# can-isolator-1_1.net
KiCad netlist of a schematic drawn in EAGLE
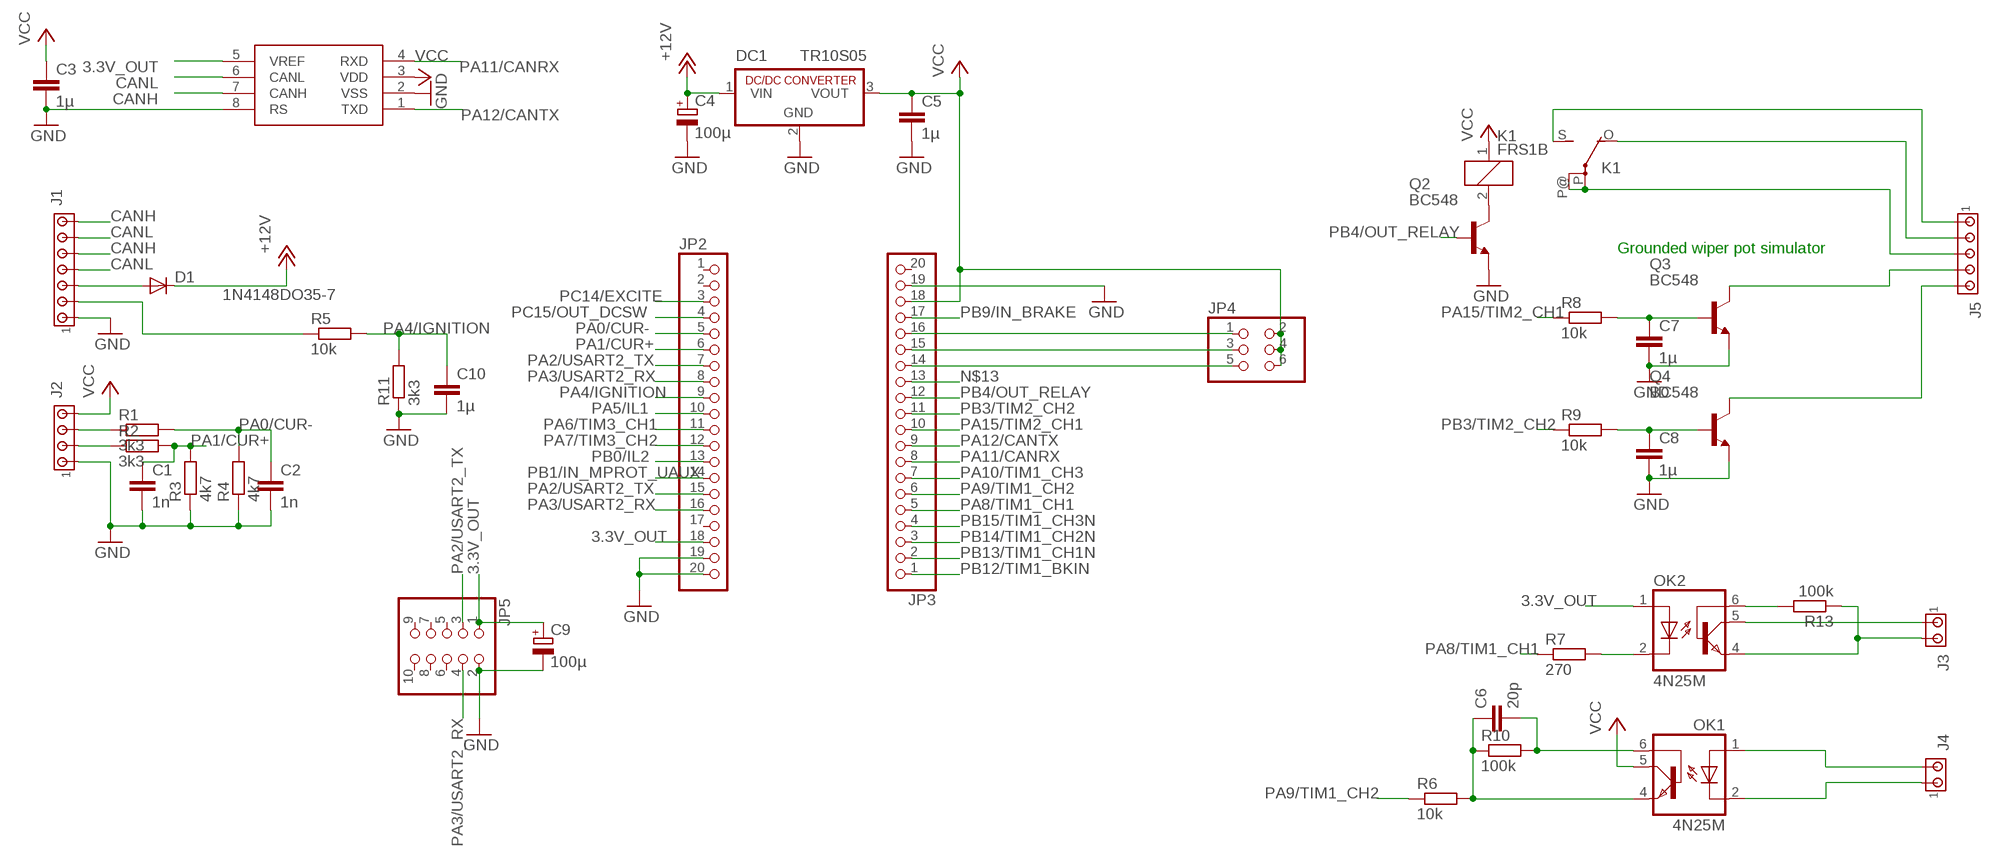
[diagram p0: schematic, sheet 1]

(export (version "E")
  (design (tool "Eeschema 10.0.6"))
  (components
    (comp (ref "C1")
      (value "1n")
      (footprint "eagle-import:C025-024X044")
      (libsource (lib "eagle-import") (part "C-EU025-024X044"))
    )
    (comp (ref "C2")
      (value "1n")
      (footprint "eagle-import:C025-024X044")
      (libsource (lib "eagle-import") (part "C-EU025-024X044"))
    )
    (comp (ref "C3")
      (value "1µ")
      (footprint "eagle-import:C025-024X044")
      (libsource (lib "eagle-import") (part "C-EU025-024X044"))
    )
    (comp (ref "C4")
      (value "100µ")
      (footprint "eagle-import:E2-5")
      (libsource (lib "eagle-import") (part "CPOL-EUE2-5"))
    )
    (comp (ref "C5")
      (value "1µ")
      (footprint "eagle-import:C025-024X044")
      (libsource (lib "eagle-import") (part "C-EU025-024X044"))
    )
    (comp (ref "C6")
      (value "20p")
      (footprint "eagle-import:C025-024X044")
      (libsource (lib "eagle-import") (part "C-EU025-024X044"))
    )
    (comp (ref "C7")
      (value "1µ")
      (footprint "eagle-import:C025-024X044")
      (libsource (lib "eagle-import") (part "C-EU025-024X044"))
    )
    (comp (ref "C8")
      (value "1µ")
      (footprint "eagle-import:C025-024X044")
      (libsource (lib "eagle-import") (part "C-EU025-024X044"))
    )
    (comp (ref "C9")
      (value "100µ")
      (footprint "eagle-import:E2-5")
      (libsource (lib "eagle-import") (part "CPOL-EUE2-5"))
    )
    (comp (ref "C10")
      (value "1µ")
      (footprint "eagle-import:C025-024X044")
      (libsource (lib "eagle-import") (part "C-EU025-024X044"))
    )
    (comp (ref "D1")
      (value "1N4148DO35-7")
      (footprint "eagle-import:DO35-7")
      (libsource (lib "eagle-import") (part "1N4148DO35-7"))
    )
    (comp (ref "DC1")
      (value "TR10S05")
      (footprint "eagle-import:SIP3")
      (libsource (lib "eagle-import") (part "R-78C-1.05.0"))
    )
    (comp (ref "IC1")
      (value "MCP2562P")
      (footprint "eagle-import:DIL08")
      (libsource (lib "eagle-import") (part "MCP2551P"))
    )
    (comp (ref "J1")
      (value "MTA07-100")
      (footprint "eagle-import:10X07MTA")
      (libsource (lib "eagle-import") (part "MTA07-100"))
    )
    (comp (ref "J2")
      (value "MTA04-100")
      (footprint "eagle-import:10X04MTA")
      (libsource (lib "eagle-import") (part "MTA04-100"))
    )
    (comp (ref "J3")
      (value "MTA02-100")
      (footprint "eagle-import:10X02MTA")
      (libsource (lib "eagle-import") (part "MTA02-100"))
    )
    (comp (ref "J4")
      (value "MTA02-100")
      (footprint "eagle-import:10X02MTA")
      (libsource (lib "eagle-import") (part "MTA02-100"))
    )
    (comp (ref "J5")
      (value "MTA05-100")
      (footprint "eagle-import:10X05MTA")
      (libsource (lib "eagle-import") (part "MTA05-100"))
    )
    (comp (ref "JP2")
      (value "PINHD-1X20")
      (footprint "eagle-import:1X20")
      (libsource (lib "eagle-import") (part "PINHD-1X20"))
    )
    (comp (ref "JP3")
      (value "PINHD-1X20")
      (footprint "eagle-import:1X20")
      (libsource (lib "eagle-import") (part "PINHD-1X20"))
    )
    (comp (ref "JP4")
      (value "PINHD-2X3")
      (footprint "eagle-import:2X03")
      (libsource (lib "eagle-import") (part "PINHD-2X3"))
    )
    (comp (ref "JP5")
      (value "PINHD-2X5/90")
      (footprint "eagle-import:2X05_90")
      (libsource (lib "eagle-import") (part "PINHD-2X5/90"))
    )
    (comp (ref "K1")
      (value "FRS1B")
      (footprint "eagle-import:FRS1B")
      (libsource (lib "eagle-import") (part "FRS1B"))
    )
    (comp (ref "OK1")
      (value "4N25M")
      (footprint "eagle-import:DIL06")
      (fields (field (name "MPN") "4N25-M"))
      (libsource (lib "eagle-import") (part "4N?M25"))
    )
    (comp (ref "OK2")
      (value "4N25M")
      (footprint "eagle-import:DIL06")
      (fields (field (name "MPN") "4N25-M"))
      (libsource (lib "eagle-import") (part "4N?M25"))
    )
    (comp (ref "Q2")
      (value "BC548")
      (footprint "eagle-import:TO92-EBC")
      (libsource (lib "eagle-import") (part "BC548"))
    )
    (comp (ref "Q3")
      (value "BC548")
      (footprint "eagle-import:TO92-EBC")
      (libsource (lib "eagle-import") (part "BC548"))
    )
    (comp (ref "Q4")
      (value "BC548")
      (footprint "eagle-import:TO92-EBC")
      (libsource (lib "eagle-import") (part "BC548"))
    )
    (comp (ref "R1")
      (value "3k3")
      (footprint "eagle-import:0207_10")
      (libsource (lib "eagle-import") (part "R-EU_0207/10"))
    )
    (comp (ref "R2")
      (value "3k3")
      (footprint "eagle-import:0207_10")
      (libsource (lib "eagle-import") (part "R-EU_0207/10"))
    )
    (comp (ref "R3")
      (value "4k7")
      (footprint "eagle-import:0207_10")
      (libsource (lib "eagle-import") (part "R-EU_0207/10"))
    )
    (comp (ref "R4")
      (value "4k7")
      (footprint "eagle-import:0207_10")
      (libsource (lib "eagle-import") (part "R-EU_0207/10"))
    )
    (comp (ref "R5")
      (value "10k")
      (footprint "eagle-import:0207_10")
      (libsource (lib "eagle-import") (part "R-EU_0207/10"))
    )
    (comp (ref "R6")
      (value "10k")
      (footprint "eagle-import:0207_10")
      (libsource (lib "eagle-import") (part "R-EU_0207/10"))
    )
    (comp (ref "R7")
      (value "270")
      (footprint "eagle-import:0207_10")
      (libsource (lib "eagle-import") (part "R-EU_0207/10"))
    )
    (comp (ref "R8")
      (value "10k")
      (footprint "eagle-import:0207_10")
      (libsource (lib "eagle-import") (part "R-EU_0207/10"))
    )
    (comp (ref "R9")
      (value "10k")
      (footprint "eagle-import:0207_10")
      (libsource (lib "eagle-import") (part "R-EU_0207/10"))
    )
    (comp (ref "R10")
      (value "100k")
      (footprint "eagle-import:0207_10")
      (libsource (lib "eagle-import") (part "R-EU_0207/10"))
    )
    (comp (ref "R11")
      (value "3k3")
      (footprint "eagle-import:0207_10")
      (libsource (lib "eagle-import") (part "R-EU_0207/10"))
    )
    (comp (ref "R13")
      (value "100k")
      (footprint "eagle-import:0207_10")
      (libsource (lib "eagle-import") (part "R-EU_0207/10"))
    )
  )
  (nets
    (net (code "1") (name "+12V") (class "Default")
      (node (ref "C4") (pin "+") (pinfunction "+_+") (pintype "passive"))
      (node (ref "D1") (pin "C") (pinfunction "C_C") (pintype "passive"))
      (node (ref "DC1") (pin "1") (pinfunction "VIN_1") (pintype "passive"))
    )
    (net (code "2") (name "/3.3V_OUT") (class "Default")
      (node (ref "C9") (pin "+") (pinfunction "+_+") (pintype "passive"))
      (node (ref "IC1") (pin "5") (pinfunction "VREF_5") (pintype "bidirectional"))
      (node (ref "JP2") (pin "18") (pinfunction "18_18") (pintype "passive"))
      (node (ref "JP5") (pin "1") (pinfunction "1_1") (pintype "passive"))
      (node (ref "OK2") (pin "1") (pinfunction "A_1") (pintype "passive"))
    )
    (net (code "3") (name "/CANH") (class "Default")
      (node (ref "IC1") (pin "7") (pinfunction "CANH_7") (pintype "bidirectional"))
      (node (ref "J1") (pin "5") (pinfunction "5_5") (pintype "passive"))
      (node (ref "J1") (pin "7") (pinfunction "7_7") (pintype "passive"))
    )
    (net (code "4") (name "/CANL") (class "Default")
      (node (ref "IC1") (pin "6") (pinfunction "CANL_6") (pintype "bidirectional"))
      (node (ref "J1") (pin "4") (pinfunction "4_4") (pintype "passive"))
      (node (ref "J1") (pin "6") (pinfunction "6_6") (pintype "passive"))
    )
    (net (code "5") (name "/N$13") (class "Default")
      (node (ref "JP3") (pin "13") (pinfunction "13_13") (pintype "passive"))
    )
    (net (code "6") (name "/PA0{slash}CUR-") (class "Default")
      (node (ref "C2") (pin "1") (pinfunction "1_1") (pintype "passive"))
      (node (ref "JP2") (pin "5") (pinfunction "5_5") (pintype "passive"))
      (node (ref "R1") (pin "2") (pinfunction "2_2") (pintype "passive"))
      (node (ref "R4") (pin "2") (pinfunction "2_2") (pintype "passive"))
    )
    (net (code "7") (name "/PA1{slash}CUR+") (class "Default")
      (node (ref "C1") (pin "1") (pinfunction "1_1") (pintype "passive"))
      (node (ref "JP2") (pin "6") (pinfunction "6_6") (pintype "passive"))
      (node (ref "R2") (pin "2") (pinfunction "2_2") (pintype "passive"))
      (node (ref "R3") (pin "2") (pinfunction "2_2") (pintype "passive"))
    )
    (net (code "8") (name "/PA2{slash}USART2_TX") (class "Default")
      (node (ref "JP2") (pin "15") (pinfunction "15_15") (pintype "passive"))
      (node (ref "JP2") (pin "7") (pinfunction "7_7") (pintype "passive"))
      (node (ref "JP5") (pin "3") (pinfunction "3_3") (pintype "passive"))
    )
    (net (code "9") (name "/PA3{slash}USART2_RX") (class "Default")
      (node (ref "JP2") (pin "16") (pinfunction "16_16") (pintype "passive"))
      (node (ref "JP2") (pin "8") (pinfunction "8_8") (pintype "passive"))
      (node (ref "JP5") (pin "4") (pinfunction "4_4") (pintype "passive"))
    )
    (net (code "10") (name "/PA4{slash}IGNITION") (class "Default")
      (node (ref "C10") (pin "1") (pinfunction "1_1") (pintype "passive"))
      (node (ref "JP2") (pin "9") (pinfunction "9_9") (pintype "passive"))
      (node (ref "R11") (pin "2") (pinfunction "2_2") (pintype "passive"))
      (node (ref "R5") (pin "2") (pinfunction "2_2") (pintype "passive"))
    )
    (net (code "11") (name "/PA5{slash}IL1") (class "Default")
      (node (ref "JP2") (pin "10") (pinfunction "10_10") (pintype "passive"))
    )
    (net (code "12") (name "/PA6{slash}TIM3_CH1") (class "Default")
      (node (ref "JP2") (pin "11") (pinfunction "11_11") (pintype "passive"))
    )
    (net (code "13") (name "/PA7{slash}TIM3_CH2") (class "Default")
      (node (ref "JP2") (pin "12") (pinfunction "12_12") (pintype "passive"))
    )
    (net (code "14") (name "/PA8{slash}TIM1_CH1") (class "Default")
      (node (ref "JP3") (pin "5") (pinfunction "5_5") (pintype "passive"))
      (node (ref "R7") (pin "1") (pinfunction "1_1") (pintype "passive"))
    )
    (net (code "15") (name "/PA9{slash}TIM1_CH2") (class "Default")
      (node (ref "JP3") (pin "6") (pinfunction "6_6") (pintype "passive"))
      (node (ref "R6") (pin "1") (pinfunction "1_1") (pintype "passive"))
    )
    (net (code "16") (name "/PA10{slash}TIM1_CH3") (class "Default")
      (node (ref "JP3") (pin "7") (pinfunction "7_7") (pintype "passive"))
    )
    (net (code "17") (name "/PA11{slash}CANRX") (class "Default")
      (node (ref "IC1") (pin "4") (pinfunction "RXD_4") (pintype "bidirectional"))
      (node (ref "JP3") (pin "8") (pinfunction "8_8") (pintype "passive"))
    )
    (net (code "18") (name "/PA12{slash}CANTX") (class "Default")
      (node (ref "IC1") (pin "1") (pinfunction "TXD_1") (pintype "bidirectional"))
      (node (ref "JP3") (pin "9") (pinfunction "9_9") (pintype "passive"))
    )
    (net (code "19") (name "/PA15{slash}TIM2_CH1") (class "Default")
      (node (ref "JP3") (pin "10") (pinfunction "10_10") (pintype "passive"))
      (node (ref "R8") (pin "1") (pinfunction "1_1") (pintype "passive"))
    )
    (net (code "20") (name "/PB0{slash}IL2") (class "Default")
      (node (ref "JP2") (pin "13") (pinfunction "13_13") (pintype "passive"))
    )
    (net (code "21") (name "/PB1{slash}IN_MPROT_UAUX") (class "Default")
      (node (ref "JP2") (pin "14") (pinfunction "14_14") (pintype "passive"))
    )
    (net (code "22") (name "/PB3{slash}TIM2_CH2") (class "Default")
      (node (ref "JP3") (pin "11") (pinfunction "11_11") (pintype "passive"))
      (node (ref "R9") (pin "1") (pinfunction "1_1") (pintype "passive"))
    )
    (net (code "23") (name "/PB4{slash}OUT_RELAY") (class "Default")
      (node (ref "JP3") (pin "12") (pinfunction "12_12") (pintype "passive"))
      (node (ref "Q2") (pin "B") (pinfunction "B_B") (pintype "passive"))
    )
    (net (code "24") (name "/PB9{slash}IN_BRAKE") (class "Default")
      (node (ref "JP3") (pin "17") (pinfunction "17_17") (pintype "passive"))
    )
    (net (code "25") (name "/PB12{slash}TIM1_BKIN") (class "Default")
      (node (ref "JP3") (pin "1") (pinfunction "1_1") (pintype "passive"))
    )
    (net (code "26") (name "/PB13{slash}TIM1_CH1N") (class "Default")
      (node (ref "JP3") (pin "2") (pinfunction "2_2") (pintype "passive"))
    )
    (net (code "27") (name "/PB14{slash}TIM1_CH2N") (class "Default")
      (node (ref "JP3") (pin "3") (pinfunction "3_3") (pintype "passive"))
    )
    (net (code "28") (name "/PB15{slash}TIM1_CH3N") (class "Default")
      (node (ref "JP3") (pin "4") (pinfunction "4_4") (pintype "passive"))
    )
    (net (code "29") (name "/PC14{slash}EXCITE") (class "Default")
      (node (ref "JP2") (pin "3") (pinfunction "3_3") (pintype "passive"))
    )
    (net (code "30") (name "/PC15{slash}OUT_DCSW") (class "Default")
      (node (ref "JP2") (pin "4") (pinfunction "4_4") (pintype "passive"))
    )
    (net (code "31") (name "GND") (class "Default")
      (node (ref "C1") (pin "2") (pinfunction "2_2") (pintype "passive"))
      (node (ref "C10") (pin "2") (pinfunction "2_2") (pintype "passive"))
      (node (ref "C2") (pin "2") (pinfunction "2_2") (pintype "passive"))
      (node (ref "C3") (pin "2") (pinfunction "2_2") (pintype "passive"))
      (node (ref "C4") (pin "-") (pinfunction "-_-") (pintype "passive"))
      (node (ref "C5") (pin "2") (pinfunction "2_2") (pintype "passive"))
      (node (ref "C7") (pin "2") (pinfunction "2_2") (pintype "passive"))
      (node (ref "C8") (pin "2") (pinfunction "2_2") (pintype "passive"))
      (node (ref "C9") (pin "-") (pinfunction "-_-") (pintype "passive"))
      (node (ref "DC1") (pin "2") (pinfunction "GND_2") (pintype "passive"))
      (node (ref "IC1") (pin "2") (pinfunction "VSS_2") (pintype "bidirectional"))
      (node (ref "IC1") (pin "8") (pinfunction "RS_8") (pintype "bidirectional"))
      (node (ref "J1") (pin "1") (pinfunction "1_1") (pintype "passive"))
      (node (ref "J2") (pin "1") (pinfunction "1_1") (pintype "passive"))
      (node (ref "JP2") (pin "19") (pinfunction "19_19") (pintype "passive"))
      (node (ref "JP2") (pin "20") (pinfunction "20_20") (pintype "passive"))
      (node (ref "JP3") (pin "19") (pinfunction "19_19") (pintype "passive"))
      (node (ref "JP5") (pin "2") (pinfunction "2_2") (pintype "passive"))
      (node (ref "Q2") (pin "E") (pinfunction "E_E") (pintype "passive"))
      (node (ref "Q3") (pin "E") (pinfunction "E_E") (pintype "passive"))
      (node (ref "Q4") (pin "E") (pinfunction "E_E") (pintype "passive"))
      (node (ref "R11") (pin "1") (pinfunction "1_1") (pintype "passive"))
      (node (ref "R3") (pin "1") (pinfunction "1_1") (pintype "passive"))
      (node (ref "R4") (pin "1") (pinfunction "1_1") (pintype "passive"))
    )
    (net (code "32") (name "Net-(C7-Pad1)") (class "Default")
      (node (ref "C7") (pin "1") (pinfunction "1_1") (pintype "passive"))
      (node (ref "Q3") (pin "B") (pinfunction "B_B") (pintype "passive"))
      (node (ref "R8") (pin "2") (pinfunction "2_2") (pintype "passive"))
    )
    (net (code "33") (name "Net-(C8-Pad1)") (class "Default")
      (node (ref "C8") (pin "1") (pinfunction "1_1") (pintype "passive"))
      (node (ref "Q4") (pin "B") (pinfunction "B_B") (pintype "passive"))
      (node (ref "R9") (pin "2") (pinfunction "2_2") (pintype "passive"))
    )
    (net (code "34") (name "Net-(D1-PadA)") (class "Default")
      (node (ref "D1") (pin "A") (pinfunction "A_A") (pintype "passive"))
      (node (ref "J1") (pin "3") (pinfunction "3_3") (pintype "passive"))
    )
    (net (code "35") (name "Net-(J1-Pad2)") (class "Default")
      (node (ref "J1") (pin "2") (pinfunction "2_2") (pintype "passive"))
      (node (ref "R5") (pin "1") (pinfunction "1_1") (pintype "passive"))
    )
    (net (code "36") (name "Net-(J2-Pad2)") (class "Default")
      (node (ref "J2") (pin "2") (pinfunction "2_2") (pintype "passive"))
      (node (ref "R2") (pin "1") (pinfunction "1_1") (pintype "passive"))
    )
    (net (code "37") (name "Net-(J2-Pad3)") (class "Default")
      (node (ref "J2") (pin "3") (pinfunction "3_3") (pintype "passive"))
      (node (ref "R1") (pin "1") (pinfunction "1_1") (pintype "passive"))
    )
    (net (code "38") (name "Net-(J5-Pad1)") (class "Default")
      (node (ref "J5") (pin "1") (pinfunction "1_1") (pintype "passive"))
      (node (ref "K1") (pin "S") (pinfunction "S_S") (pintype "passive"))
    )
    (net (code "39") (name "Net-(J5-Pad2)") (class "Default")
      (node (ref "J5") (pin "2") (pinfunction "2_2") (pintype "passive"))
      (node (ref "K1") (pin "O") (pinfunction "O_O") (pintype "passive"))
    )
    (net (code "40") (name "Net-(J5-Pad3)") (class "Default")
      (node (ref "J5") (pin "3") (pinfunction "3_3") (pintype "passive"))
      (node (ref "K1") (pin "P") (pinfunction "P_P") (pintype "passive"))
      (node (ref "K1") (pin "P@") (pinfunction "P_P@") (pintype "passive"))
    )
    (net (code "41") (name "Net-(J5-Pad4)") (class "Default")
      (node (ref "J5") (pin "4") (pinfunction "4_4") (pintype "passive"))
      (node (ref "Q3") (pin "C") (pinfunction "C_C") (pintype "passive"))
    )
    (net (code "42") (name "Net-(J5-Pad5)") (class "Default")
      (node (ref "J5") (pin "5") (pinfunction "5_5") (pintype "passive"))
      (node (ref "Q4") (pin "C") (pinfunction "C_C") (pintype "passive"))
    )
    (net (code "43") (name "Net-(JP3-Pad14)") (class "Default")
      (node (ref "JP3") (pin "14") (pinfunction "14_14") (pintype "passive"))
      (node (ref "JP4") (pin "5") (pinfunction "5_5") (pintype "passive"))
    )
    (net (code "44") (name "Net-(JP3-Pad15)") (class "Default")
      (node (ref "JP3") (pin "15") (pinfunction "15_15") (pintype "passive"))
      (node (ref "JP4") (pin "3") (pinfunction "3_3") (pintype "passive"))
    )
    (net (code "45") (name "Net-(JP3-Pad16)") (class "Default")
      (node (ref "JP3") (pin "16") (pinfunction "16_16") (pintype "passive"))
      (node (ref "JP4") (pin "1") (pinfunction "1_1") (pintype "passive"))
    )
    (net (code "46") (name "Net-(K1-Pad2)") (class "Default")
      (node (ref "K1") (pin "2") (pinfunction "2_2") (pintype "passive"))
      (node (ref "Q2") (pin "C") (pinfunction "C_C") (pintype "passive"))
    )
    (net (code "47") (name "Net-(OK1-A)") (class "Default")
      (node (ref "J4") (pin "2") (pinfunction "2_2") (pintype "passive"))
      (node (ref "OK1") (pin "1") (pinfunction "A_1") (pintype "passive"))
    )
    (net (code "48") (name "Net-(OK1-BAS)") (class "Default")
      (node (ref "C6") (pin "2") (pinfunction "2_2") (pintype "passive"))
      (node (ref "OK1") (pin "6") (pinfunction "BAS_6") (pintype "passive"))
      (node (ref "R10") (pin "2") (pinfunction "2_2") (pintype "passive"))
    )
    (net (code "49") (name "Net-(OK1-C)") (class "Default")
      (node (ref "J4") (pin "1") (pinfunction "1_1") (pintype "passive"))
      (node (ref "OK1") (pin "2") (pinfunction "C_2") (pintype "passive"))
    )
    (net (code "50") (name "Net-(OK1-EMI)") (class "Default")
      (node (ref "C6") (pin "1") (pinfunction "1_1") (pintype "passive"))
      (node (ref "OK1") (pin "4") (pinfunction "EMI_4") (pintype "passive"))
      (node (ref "R10") (pin "1") (pinfunction "1_1") (pintype "passive"))
      (node (ref "R6") (pin "2") (pinfunction "2_2") (pintype "passive"))
    )
    (net (code "51") (name "Net-(OK2-BAS)") (class "Default")
      (node (ref "OK2") (pin "6") (pinfunction "BAS_6") (pintype "passive"))
      (node (ref "R13") (pin "2") (pinfunction "2_2") (pintype "passive"))
    )
    (net (code "52") (name "Net-(OK2-C)") (class "Default")
      (node (ref "OK2") (pin "2") (pinfunction "C_2") (pintype "passive"))
      (node (ref "R7") (pin "2") (pinfunction "2_2") (pintype "passive"))
    )
    (net (code "53") (name "Net-(OK2-COL)") (class "Default")
      (node (ref "J3") (pin "1") (pinfunction "1_1") (pintype "passive"))
      (node (ref "OK2") (pin "5") (pinfunction "COL_5") (pintype "passive"))
    )
    (net (code "54") (name "Net-(OK2-EMI)") (class "Default")
      (node (ref "J3") (pin "2") (pinfunction "2_2") (pintype "passive"))
      (node (ref "OK2") (pin "4") (pinfunction "EMI_4") (pintype "passive"))
      (node (ref "R13") (pin "1") (pinfunction "1_1") (pintype "passive"))
    )
    (net (code "55") (name "VCC") (class "Default")
      (node (ref "C3") (pin "1") (pinfunction "1_1") (pintype "passive"))
      (node (ref "C5") (pin "1") (pinfunction "1_1") (pintype "passive"))
      (node (ref "DC1") (pin "3") (pinfunction "VOUT_3") (pintype "passive"))
      (node (ref "IC1") (pin "3") (pinfunction "VDD_3") (pintype "bidirectional"))
      (node (ref "J2") (pin "4") (pinfunction "4_4") (pintype "passive"))
      (node (ref "JP3") (pin "18") (pinfunction "18_18") (pintype "passive"))
      (node (ref "JP4") (pin "2") (pinfunction "2_2") (pintype "passive"))
      (node (ref "JP4") (pin "4") (pinfunction "4_4") (pintype "passive"))
      (node (ref "JP4") (pin "6") (pinfunction "6_6") (pintype "passive"))
      (node (ref "K1") (pin "1") (pinfunction "1_1") (pintype "passive"))
      (node (ref "OK1") (pin "5") (pinfunction "COL_5") (pintype "passive"))
    )
    (net (code "56") (name "unconnected-(JP2-Pad1)") (class "Default")
      (node (ref "JP2") (pin "1") (pinfunction "1_1") (pintype "passive"))
    )
    (net (code "57") (name "unconnected-(JP2-Pad2)") (class "Default")
      (node (ref "JP2") (pin "2") (pinfunction "2_2") (pintype "passive"))
    )
    (net (code "58") (name "unconnected-(JP2-Pad17)") (class "Default")
      (node (ref "JP2") (pin "17") (pinfunction "17_17") (pintype "passive"))
    )
    (net (code "59") (name "unconnected-(JP3-Pad20)") (class "Default")
      (node (ref "JP3") (pin "20") (pinfunction "20_20") (pintype "passive"))
    )
    (net (code "60") (name "unconnected-(JP5-Pad5)") (class "Default")
      (node (ref "JP5") (pin "5") (pinfunction "5_5") (pintype "passive"))
    )
    (net (code "61") (name "unconnected-(JP5-Pad6)") (class "Default")
      (node (ref "JP5") (pin "6") (pinfunction "6_6") (pintype "passive"))
    )
    (net (code "62") (name "unconnected-(JP5-Pad7)") (class "Default")
      (node (ref "JP5") (pin "7") (pinfunction "7_7") (pintype "passive"))
    )
    (net (code "63") (name "unconnected-(JP5-Pad8)") (class "Default")
      (node (ref "JP5") (pin "8") (pinfunction "8_8") (pintype "passive"))
    )
    (net (code "64") (name "unconnected-(JP5-Pad9)") (class "Default")
      (node (ref "JP5") (pin "9") (pinfunction "9_9") (pintype "passive"))
    )
    (net (code "65") (name "unconnected-(JP5-Pad10)") (class "Default")
      (node (ref "JP5") (pin "10") (pinfunction "10_10") (pintype "passive"))
    )
  )
)
